# casagrande_v1.net
KiCad netlist of a schematic drawn in EAGLE
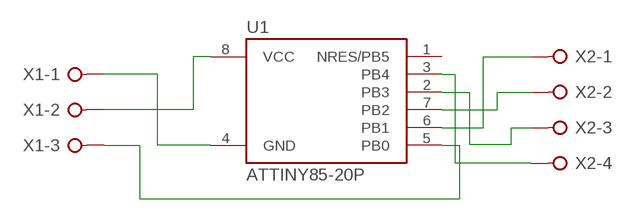
[diagram p0: schematic, sheet 1]

(export (version "E")
  (design (tool "Eeschema 10.0.6"))
  (components
    (comp (ref "U1")
      (value "ATTINY85-20P")
      (footprint "eagle-import:PDIP08_300MIL")
      (libsource (lib "eagle-import") (part "ATTINY85P-20"))
    )
    (comp (ref "X1")
      (value "W237-03P")
      (footprint "eagle-import:W237-133")
      (libsource (lib "eagle-import") (part "W237-03P"))
    )
    (comp (ref "X2")
      (value "W237-04P")
      (footprint "eagle-import:W237-4P")
      (libsource (lib "eagle-import") (part "W237-04P"))
    )
  )
  (nets
    (net (code "1") (name "Net-(U1-GND)") (class "Default")
      (node (ref "U1") (pin "4") (pinfunction "GND_4") (pintype "power_in"))
      (node (ref "X1") (pin "1") (pinfunction "KL_1") (pintype "passive"))
    )
    (net (code "2") (name "Net-(U1-PB0)") (class "Default")
      (node (ref "U1") (pin "5") (pinfunction "PB0_5") (pintype "bidirectional"))
      (node (ref "X1") (pin "3") (pinfunction "KL_3") (pintype "passive"))
    )
    (net (code "3") (name "Net-(U1-PB1)") (class "Default")
      (node (ref "U1") (pin "6") (pinfunction "PB1_6") (pintype "bidirectional"))
      (node (ref "X2") (pin "1") (pinfunction "KL_1") (pintype "passive"))
    )
    (net (code "4") (name "Net-(U1-PB2)") (class "Default")
      (node (ref "U1") (pin "7") (pinfunction "PB2_7") (pintype "bidirectional"))
      (node (ref "X2") (pin "2") (pinfunction "KL_2") (pintype "passive"))
    )
    (net (code "5") (name "Net-(U1-PB3)") (class "Default")
      (node (ref "U1") (pin "2") (pinfunction "PB3_2") (pintype "bidirectional"))
      (node (ref "X2") (pin "3") (pinfunction "KL_3") (pintype "passive"))
    )
    (net (code "6") (name "Net-(U1-PB4)") (class "Default")
      (node (ref "U1") (pin "3") (pinfunction "PB4_3") (pintype "bidirectional"))
      (node (ref "X2") (pin "4") (pinfunction "KL_4") (pintype "passive"))
    )
    (net (code "7") (name "Net-(U1-VCC)") (class "Default")
      (node (ref "U1") (pin "8") (pinfunction "VCC_8") (pintype "power_in"))
      (node (ref "X1") (pin "2") (pinfunction "KL_2") (pintype "passive"))
    )
    (net (code "8") (name "unconnected-(U1-NRES{slash}PB5-Pad1)") (class "Default")
      (node (ref "U1") (pin "1") (pinfunction "NRES/PB5_1") (pintype "bidirectional"))
    )
  )
)
